# ProProject_2024__2024-10-06.net
KiCad netlist of a schematic drawn in EasyEDA Pro
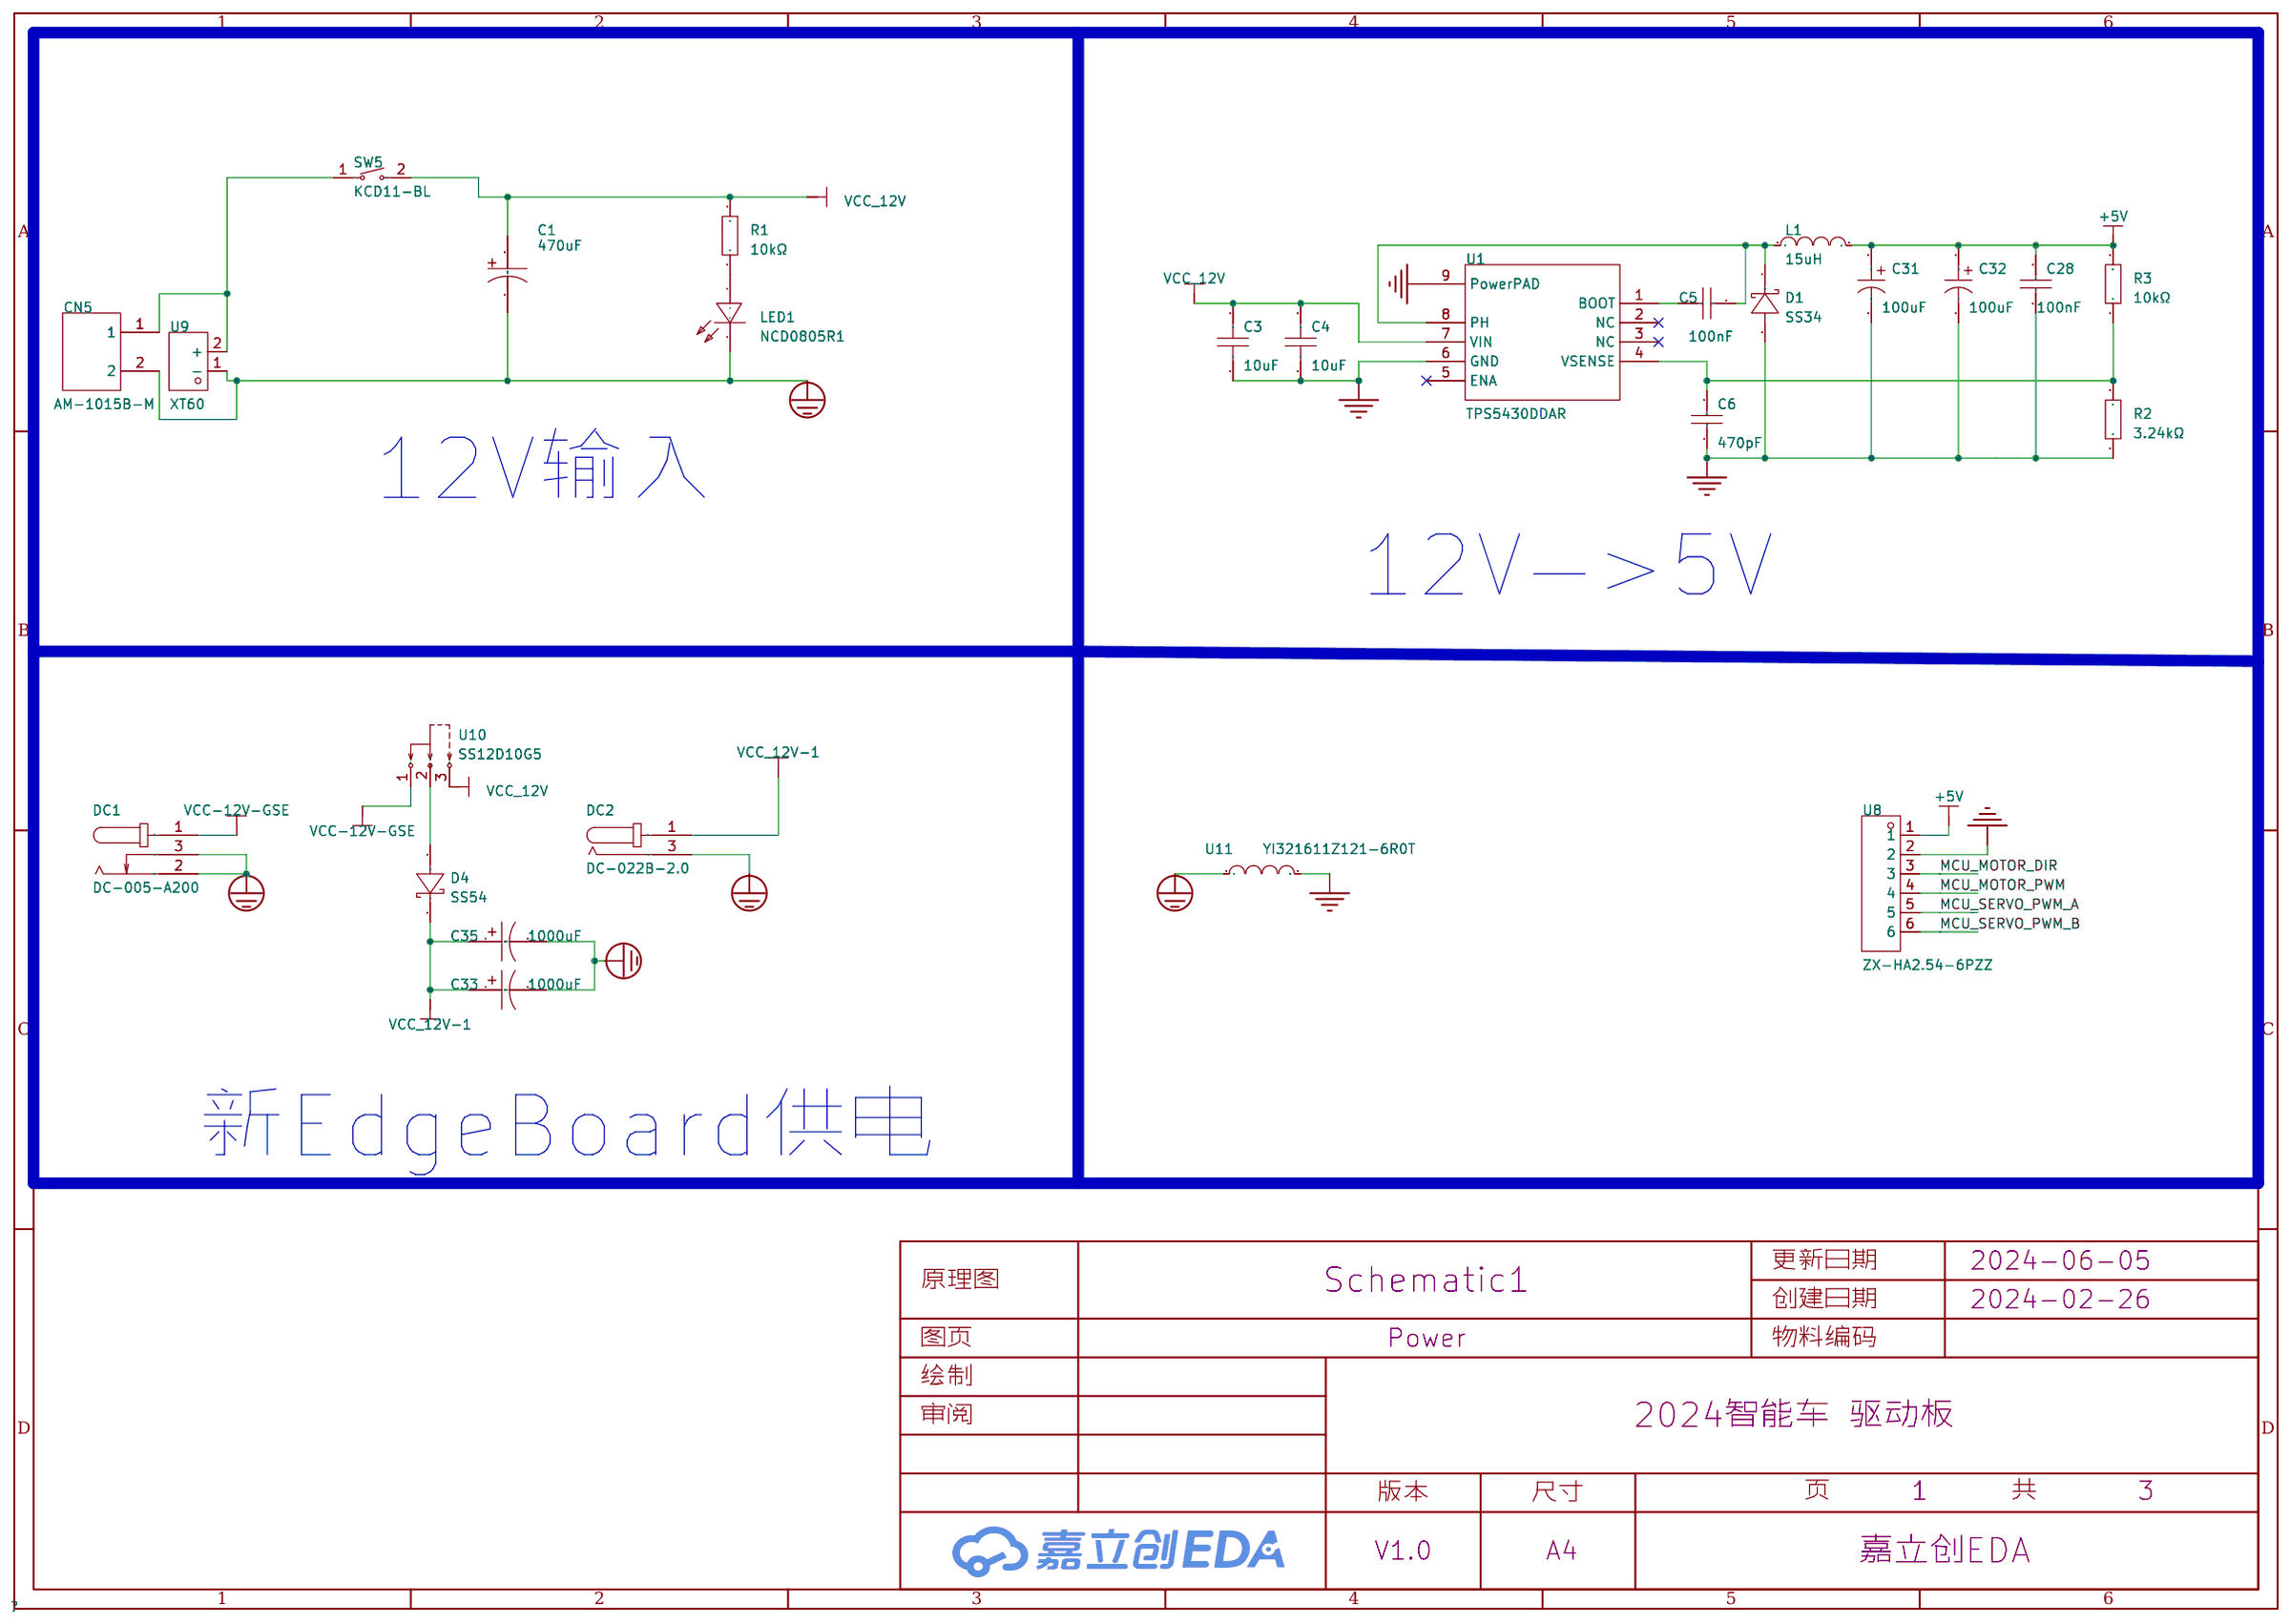
[diagram p0: Power]
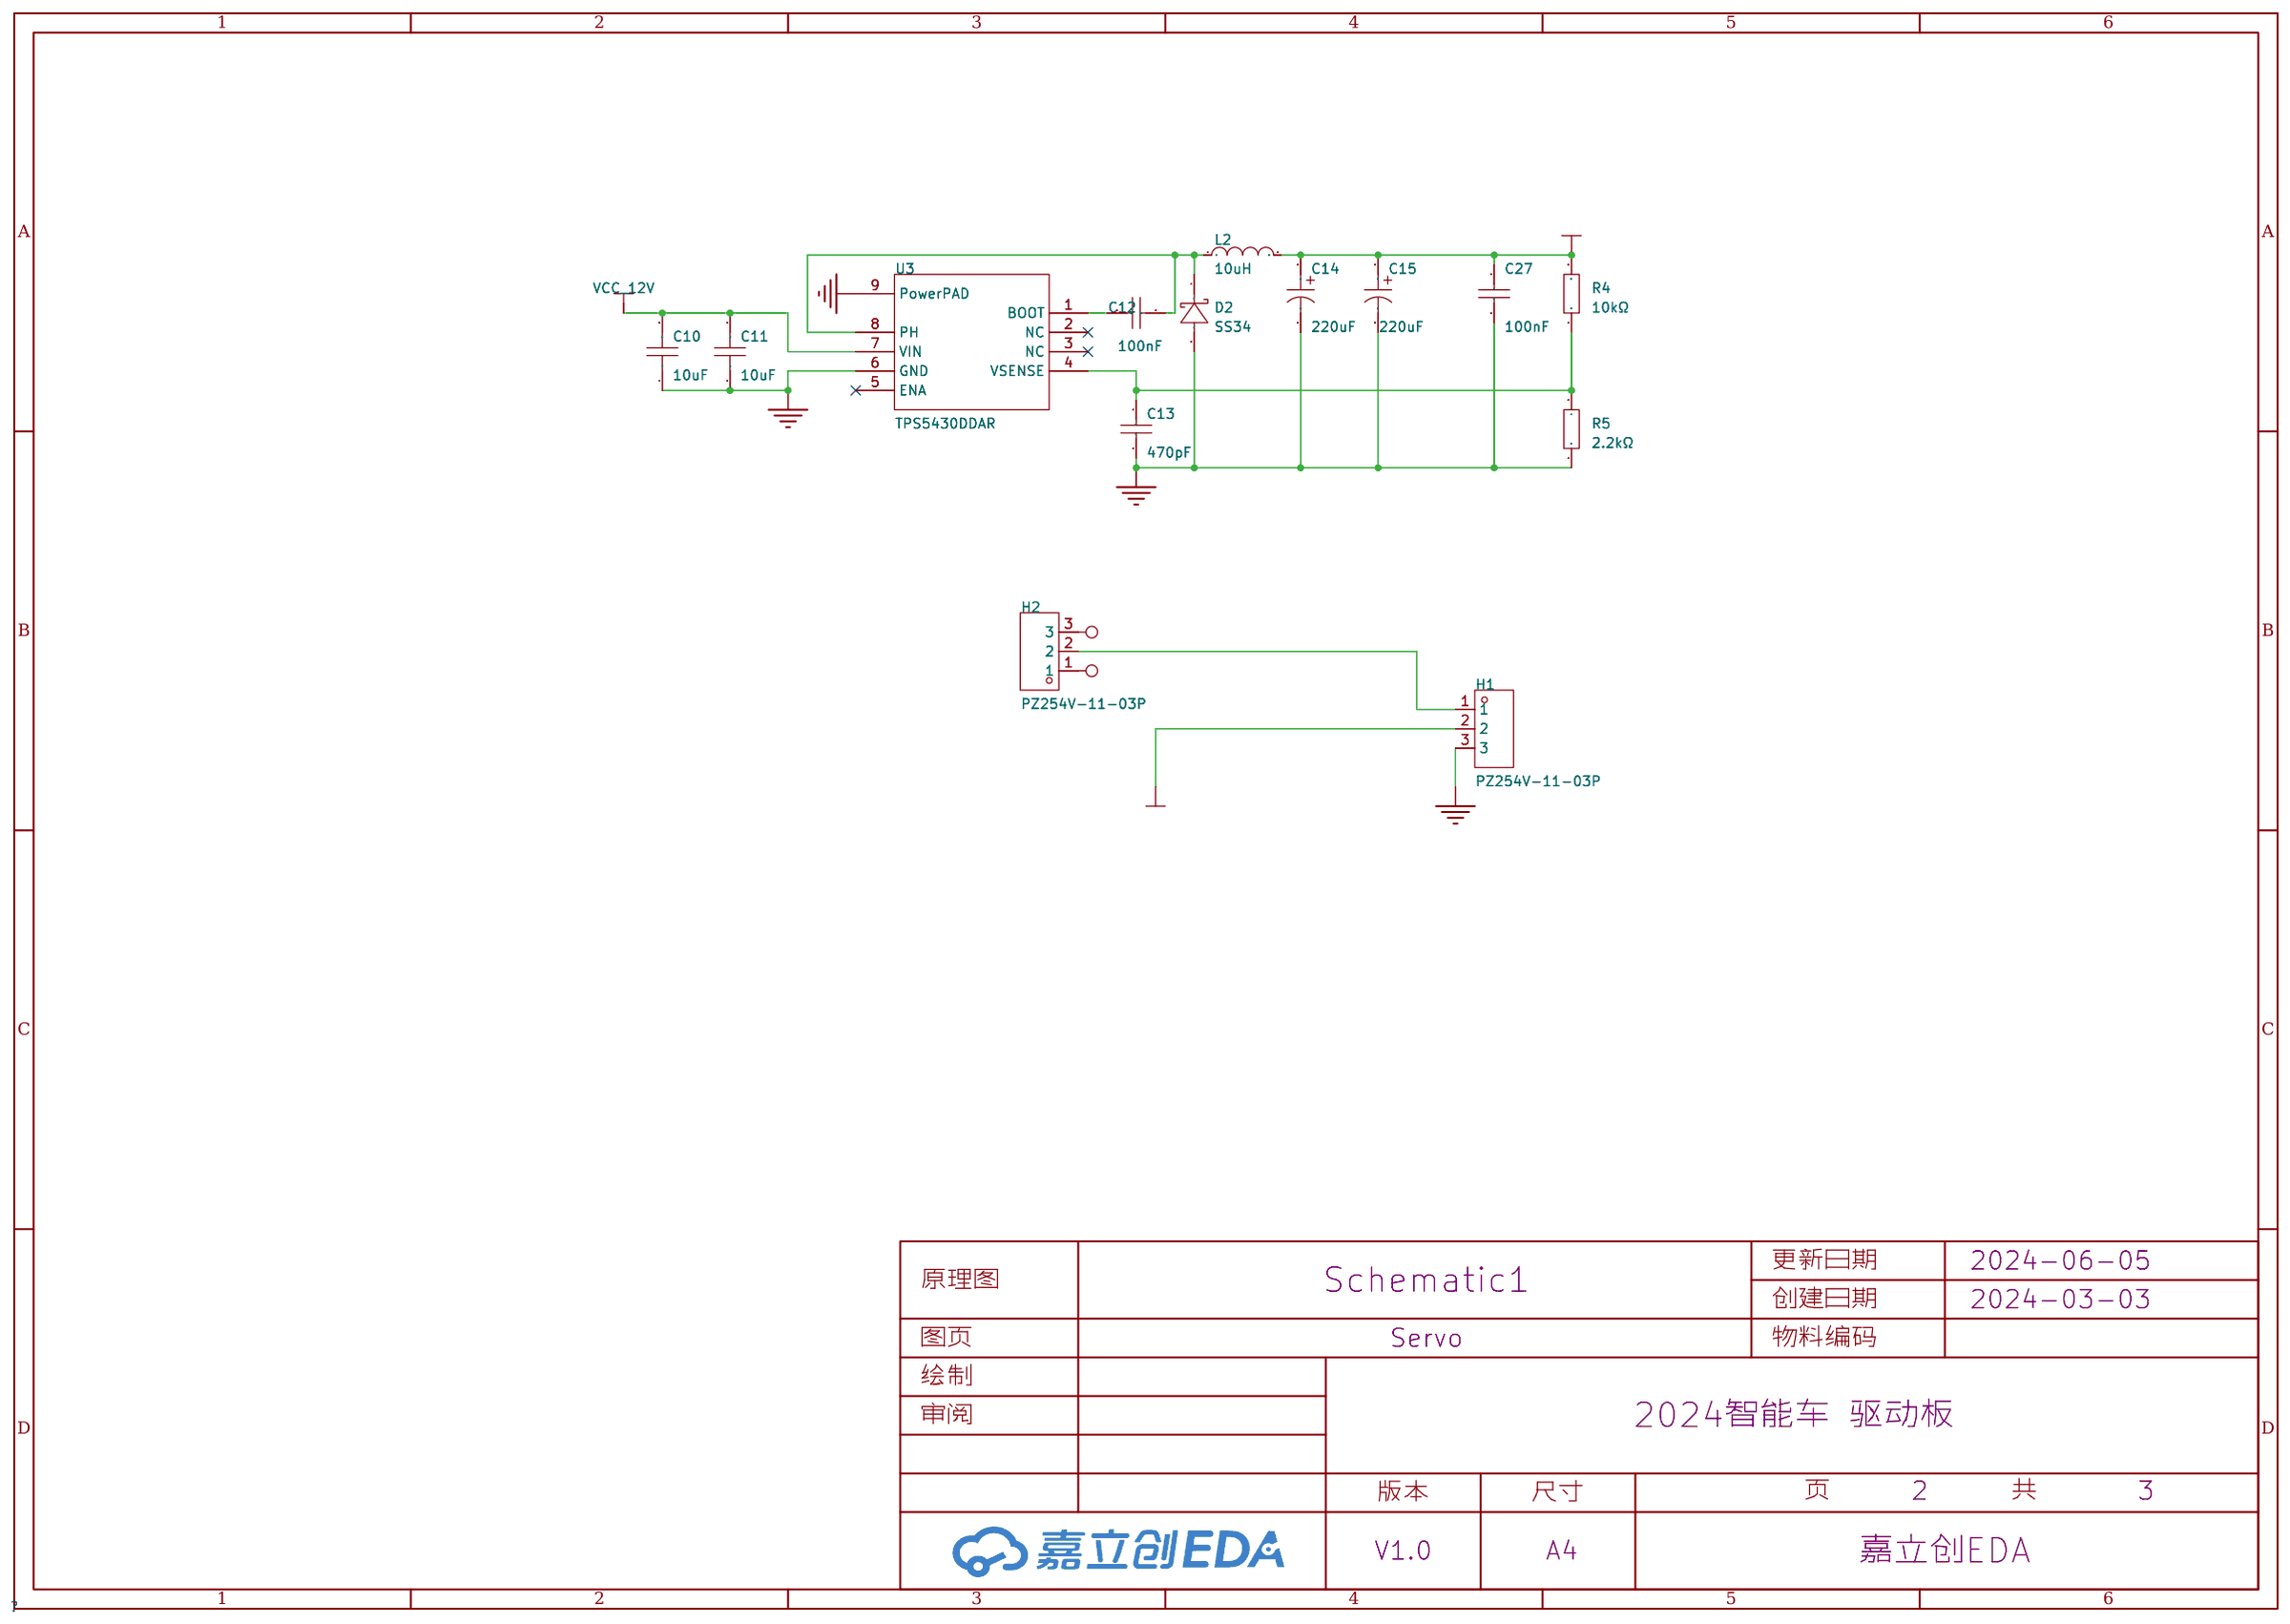
[diagram p1: Servo]
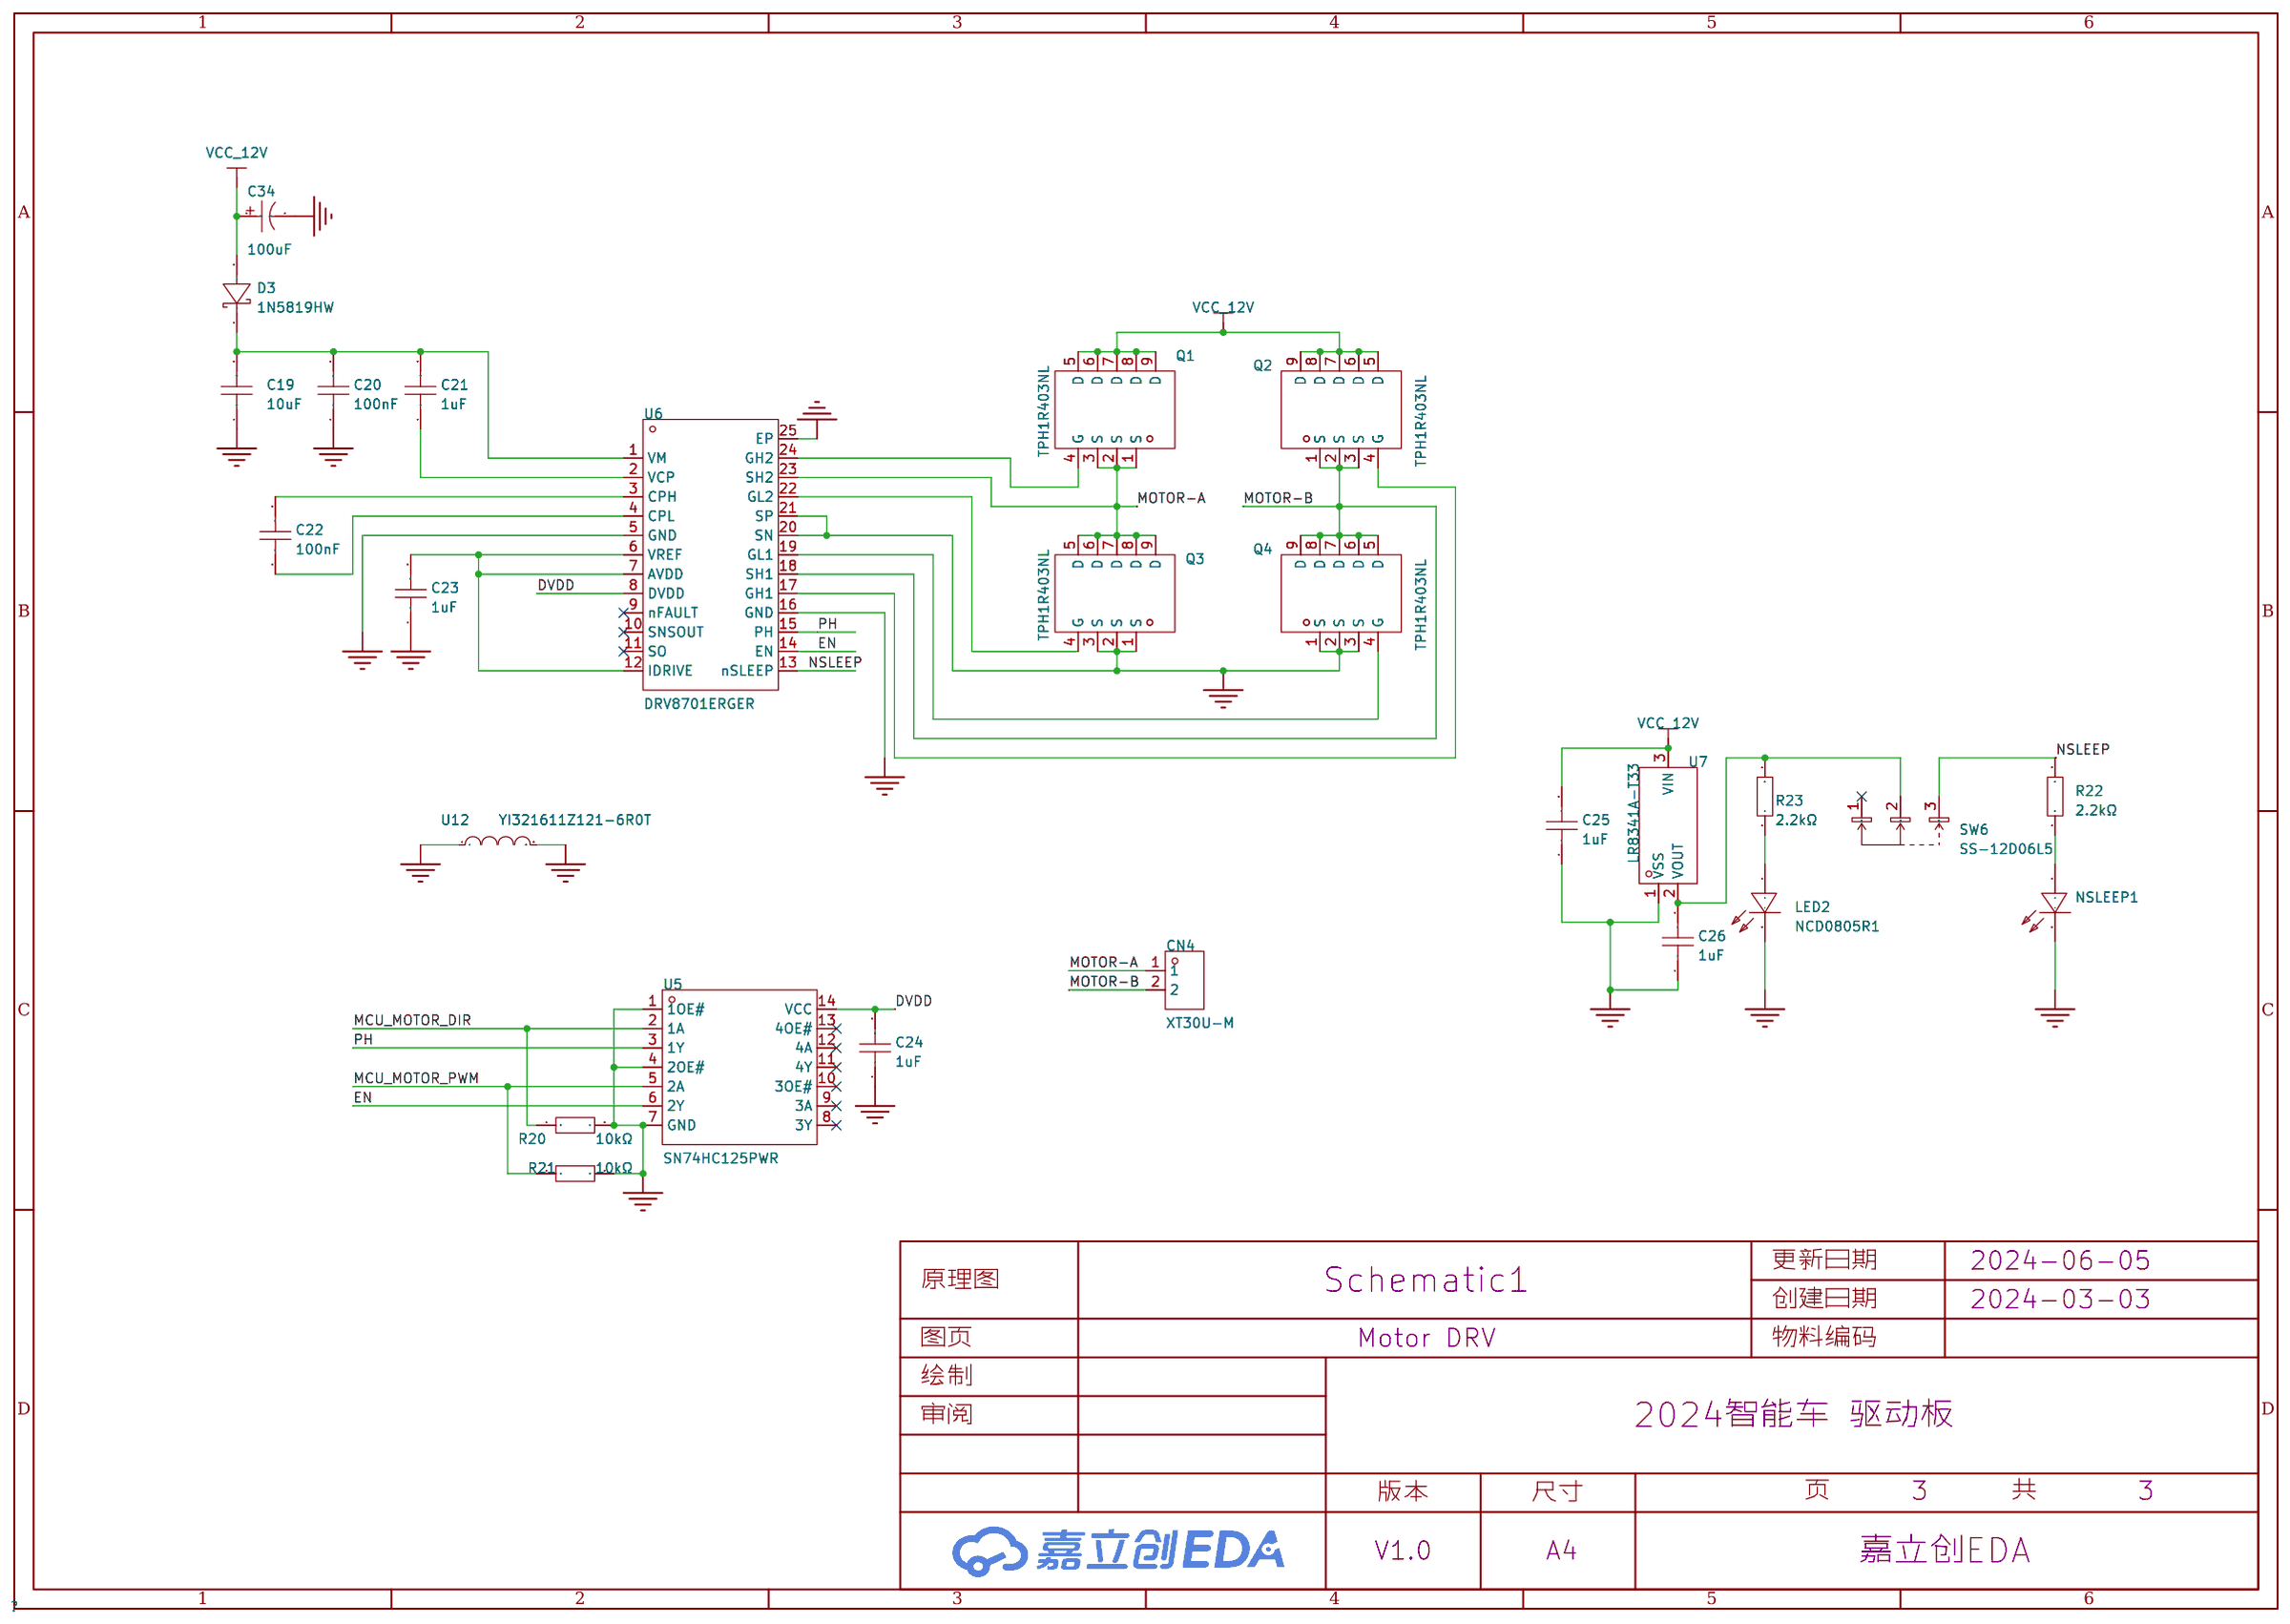
[diagram p2: Motor DRV]

(export (version "E")
  (design (tool "Eeschema 10.0.6"))
  (components
    (comp (ref "C1")
      (value "470uF")
      (footprint "easyedapro:CAP-TH_BD8.0-P3.50-D0.6-FD")
      (description "容值:470uF;精度:±20%;额定电压:25V;纹波电流:250mA@100kHz;等效串联电阻:-;")
      (fields
        (field (name "Manufacturer Part") "01EC1227SHC470UF25V")
        (field (name "Manufacturer") "KNSCHA(科尼盛)")
      )
      (libsource (lib "easyedapro") (part "01EC1227SHC470UF25V"))
    )
    (comp (ref "C3")
      (value "10uF")
      (footprint "easyedapro:C0805")
      (description "容值:10uF;精度:±10%;额定电压:25V;材质(温度系数):X5R;")
      (fields
        (field (name "Manufacturer Part") "CL21A106KAYNNNE")
        (field (name "Manufacturer") "SAMSUNG(三星)")
      )
      (libsource (lib "easyedapro") (part "CL21A106KAYNNNE"))
    )
    (comp (ref "C4")
      (value "10uF")
      (footprint "easyedapro:C0805")
      (description "容值:10uF;精度:±10%;额定电压:25V;材质(温度系数):X5R;")
      (fields
        (field (name "Manufacturer Part") "CL21A106KAYNNNE")
        (field (name "Manufacturer") "SAMSUNG(三星)")
      )
      (libsource (lib "easyedapro") (part "CL21A106KAYNNNE"))
    )
    (comp (ref "C5")
      (value "100nF")
      (footprint "easyedapro:C0603")
      (description "容值:100nF;精度:±10%;额定电压:50V;材质(温度系数):X7R;")
      (fields (field (name "Manufacturer Part") "0603B104K500NT") (field (name "Manufacturer") "FH(风华)"))
      (libsource (lib "easyedapro") (part "0603B104K500NT"))
    )
    (comp (ref "C6")
      (value "470pF")
      (footprint "easyedapro:C0603")
      (description "容值:470pF;精度:±10%;额定电压:50V;材质(温度系数):X7R;")
      (fields (field (name "Manufacturer Part") "0603B471K500NT") (field (name "Manufacturer") "FH(风华)"))
      (libsource (lib "easyedapro") (part "0603B471K500NT"))
    )
    (comp (ref "C28")
      (value "100nF")
      (footprint "easyedapro:C0603")
      (description "容值:100nF;精度:±10%;额定电压:50V;材质(温度系数):X7R;")
      (fields (field (name "Manufacturer Part") "0603B104K500NT") (field (name "Manufacturer") "FH(风华)"))
      (libsource (lib "easyedapro") (part "0603B104K500NT"))
    )
    (comp (ref "C31")
      (value "100uF")
      (footprint "easyedapro:CAP-SMD_BD6.3-L6.6-W6.6-LS7.2-FD")
      (description "容值:100uF;精度:±20%;额定电压:16V;纹波电流:93mA@120Hz;等效串联电阻:-;")
      (fields
        (field (name "Manufacturer Part") "RVT100UF16V67RV0016")
        (field (name "Manufacturer") "KNSCHA(科尼盛)")
      )
      (libsource (lib "easyedapro") (part "RVT100UF16V67RV0016"))
    )
    (comp (ref "C32")
      (value "100uF")
      (footprint "easyedapro:CAP-SMD_BD6.3-L6.6-W6.6-LS7.2-FD")
      (description "容值:100uF;精度:±20%;额定电压:16V;纹波电流:93mA@120Hz;等效串联电阻:-;")
      (fields
        (field (name "Manufacturer Part") "RVT100UF16V67RV0016")
        (field (name "Manufacturer") "KNSCHA(科尼盛)")
      )
      (libsource (lib "easyedapro") (part "RVT100UF16V67RV0016"))
    )
    (comp (ref "C33")
      (value "1000uF")
      (footprint "easyedapro:CAP-TH_BD13.0-P5.00-D0.6-FD")
      (description "容值:1000uF;精度:±20%;额定电压:35V;纹波电流:-;等效串联电阻:-;")
      (fields
        (field (name "Manufacturer Part") "SHF1000UF35V01EC4584")
        (field (name "Manufacturer") "KNSCHA(科尼盛)")
      )
      (libsource (lib "easyedapro") (part "SHF1000UF35V01EC4584"))
    )
    (comp (ref "C35")
      (value "1000uF")
      (footprint "easyedapro:CAP-TH_BD13.0-P5.00-D0.6-FD")
      (description "容值:1000uF;精度:±20%;额定电压:35V;纹波电流:-;等效串联电阻:-;")
      (fields
        (field (name "Manufacturer Part") "SHF1000UF35V01EC4584")
        (field (name "Manufacturer") "KNSCHA(科尼盛)")
      )
      (libsource (lib "easyedapro") (part "SHF1000UF35V01EC4584"))
    )
    (comp (ref "CN5")
      (value "AM-1015B-M")
      (footprint "easyedapro:CONN-TH_AM-1015B-M")
      (description "类别:-;类型1:-;")
      (fields (field (name "Manufacturer") "AMASS(艾迈斯)"))
      (libsource (lib "easyedapro") (part "AM-1015B-M"))
    )
    (comp (ref "D1")
      (value "SS34")
      (footprint "easyedapro:SMA_L4.3-W2.5-LS5.0-RD")
      (description "二极管配置:独立式;正向压降(Vf):550mV@3A;直流反向耐压(Vr):40V;平均整流电流(Io):3A;")
      (fields (field (name "Manufacturer") "TWGMC(台湾迪嘉)"))
      (libsource (lib "easyedapro") (part "SS34_C727060"))
    )
    (comp (ref "D4")
      (value "SS54")
      (footprint "easyedapro:SMA_L4.3-W2.6-LS5.0-RD")
      (description "二极管配置:独立式;正向压降(Vf):550mV@5A;直流反向耐压(Vr):40V;平均整流电流(Io):5A;")
      (fields (field (name "Manufacturer") "TWGMC(台湾迪嘉)"))
      (libsource (lib "easyedapro") (part "SS54_C727065"))
    )
    (comp (ref "DC1")
      (value "DC-005-A200")
      (footprint "easyedapro:DC-IN-TH_DC-005-A200")
      (description "连接器类型:DC电源插座;安装方式:弯插;触点内径:2mm;触点外径:6.4mm;额定电流:3A;额定电压:30V;工作温度范围:-20°C~+70°C;")
      (fields (field (name "Manufacturer") "XUNPU(讯普)"))
      (libsource (lib "easyedapro") (part "DC-005-A200"))
    )
    (comp (ref "DC2")
      (value "DC-022B-2.0")
      (footprint "easyedapro:DC-IN-TH_DC-022B-2.0")
      (fields (field (name "Manufacturer") "XKB Connectivity(中国星坤)"))
      (libsource (lib "easyedapro") (part "DC-022B-2.0"))
    )
    (comp (ref "L1")
      (value "15uH")
      (footprint "easyedapro:IND-SMD_L7.0-W6.6_FXL0630")
      (description "电感值:15uH;精度:±20%;额定电流:3A;饱和电流(Isat):4.5A;类型:一体成型电感;")
      (fields (field (name "Manufacturer Part") "FXL0630-150-M") (field (name "Manufacturer") "cjiang(长江微电)"))
      (libsource (lib "easyedapro") (part "FXL0630-150-M"))
    )
    (comp (ref "LED1")
      (value "NCD0805R1")
      (footprint "easyedapro:LED0805-R-RD")
      (fields (field (name "Manufacturer") "国星光电"))
      (libsource (lib "easyedapro") (part "FC-2012HRK-620D"))
    )
    (comp (ref "R1")
      (value "10kΩ")
      (footprint "easyedapro:R0805")
      (description "电阻类型:厚膜电阻;阻值:10kΩ;精度:±1%;功率:125mW;最大工作电压:150V;温度系数:±100ppm/°C;")
      (fields
        (field (name "Manufacturer Part") "0805W8F1002T5E")
        (field (name "Manufacturer") "UNI-ROYAL(厚声)")
      )
      (libsource (lib "easyedapro") (part "0805W8F1002T5E"))
    )
    (comp (ref "R2")
      (value "3.24kΩ")
      (footprint "easyedapro:R0603")
      (description "电阻类型:厚膜电阻;阻值:3.24kΩ;精度:±1%;功率:100mW;最大工作电压:75V;温度系数:±100ppm/°C;")
      (fields
        (field (name "Manufacturer Part") "0603WAF3241T5E")
        (field (name "Manufacturer") "UNI-ROYAL(厚声)")
      )
      (libsource (lib "easyedapro") (part "0603WAF3241T5E"))
    )
    (comp (ref "R3")
      (value "10kΩ")
      (footprint "easyedapro:R0603")
      (description "电阻类型:厚膜电阻;阻值:10kΩ;精度:±1%;功率:100mW;最大工作电压:75V;温度系数:±100ppm/°C;")
      (fields
        (field (name "Manufacturer Part") "0603WAF1002T5E")
        (field (name "Manufacturer") "UNI-ROYAL(厚声)")
      )
      (libsource (lib "easyedapro") (part "0603WAF1002T5E"))
    )
    (comp (ref "SW5")
      (value "KCD11-BL")
      (footprint "easyedapro:SW-TH_KCD11-BL")
      (description "带灯:无;引脚样式:焊片;额定电流:3A;额定电压(AC):250V;额定电压(DC):-;电路结构:单刀单掷;机械寿命:1万次;")
      (fields (field (name "Manufacturer") "SHOU HAN(首韩)"))
      (libsource (lib "easyedapro") (part "KCD11-BL"))
    )
    (comp (ref "U1")
      (value "TPS5430DDAR")
      (footprint "easyedapro:ESOP-8_L4.9-W3.9-P1.27-LS6.0-TL-EP")
      (description "功能类型:降压型;输出类型:可调;输入电压:5.5V~36V;输出电压:1.221V~32.04V;输出电流(最大值):3A;")
      (fields (field (name "Manufacturer") "TI(德州仪器)"))
      (libsource (lib "easyedapro") (part "TPS5430DDAR"))
    )
    (comp (ref "U8")
      (value "ZX-HA2.54-6PZZ")
      (footprint "easyedapro:CONN-TH_6P-P2.50_ZX-HA2.54-6PZZ")
      (fields (field (name "Manufacturer") "Megastar(兆星)"))
      (libsource (lib "easyedapro") (part "ZX-HA2.54-6PZZ"))
    )
    (comp (ref "U9")
      (value "XT60")
      (footprint "easyedapro:CONN-TH_XT60")
      (description "类别:-;类型1:-;")
      (fields (field (name "Manufacturer") "AMASS(艾迈斯)"))
      (libsource (lib "easyedapro") (part "XT60"))
    )
    (comp (ref "U10")
      (value "SS12D10G5")
      (footprint "easyedapro:SW-TH_SHOU-HAN_SS12D10G4")
      (description "电路结构:单刀双掷;安装方式:直插;额定电流(DC):2A;额定电压(DC):125V;机械寿命:3千次;")
      (fields (field (name "Manufacturer") "SHOU HAN(首韩)"))
      (libsource (lib "easyedapro") (part "SS12D10G5"))
    )
    (comp (ref "U11")
      (value "YI321611Z121-6R0T")
      (footprint "easyedapro:L1206")
      (description "标称阻抗@测试频率:120Ω@100MHz;误差:±25%;直流电阻(RDC):20mΩ;")
      (fields (field (name "Manufacturer") "YJYCOIN(益嘉源)"))
      (libsource (lib "easyedapro") (part "YI321611Z121-6R0T"))
    )
    (comp (ref "C10")
      (value "10uF")
      (footprint "easyedapro:C0805")
      (description "容值:10uF;精度:±10%;额定电压:25V;材质(温度系数):X5R;")
      (fields
        (field (name "Manufacturer Part") "CL21A106KAYNNNE")
        (field (name "Manufacturer") "SAMSUNG(三星)")
      )
      (libsource (lib "easyedapro") (part "CL21A106KAYNNNE"))
    )
    (comp (ref "C11")
      (value "10uF")
      (footprint "easyedapro:C0805")
      (description "容值:10uF;精度:±10%;额定电压:25V;材质(温度系数):X5R;")
      (fields
        (field (name "Manufacturer Part") "CL21A106KAYNNNE")
        (field (name "Manufacturer") "SAMSUNG(三星)")
      )
      (libsource (lib "easyedapro") (part "CL21A106KAYNNNE"))
    )
    (comp (ref "C12")
      (value "100nF")
      (footprint "easyedapro:C0603")
      (description "容值:100nF;精度:±10%;额定电压:50V;材质(温度系数):X7R;")
      (fields (field (name "Manufacturer Part") "0603B104K500NT") (field (name "Manufacturer") "FH(风华)"))
      (libsource (lib "easyedapro") (part "0603B104K500NT"))
    )
    (comp (ref "C13")
      (value "470pF")
      (footprint "easyedapro:C0603")
      (description "容值:470pF;精度:±10%;额定电压:50V;材质(温度系数):X7R;")
      (fields (field (name "Manufacturer Part") "0603B471K500NT") (field (name "Manufacturer") "FH(风华)"))
      (libsource (lib "easyedapro") (part "0603B471K500NT"))
    )
    (comp (ref "C14")
      (value "220uF")
      (footprint "easyedapro:CAP-SMD_BD6.3-L6.6-W6.6-FD")
      (description "容值:220uF;精度:±20%;额定电压:16V;纹波电流:110mA@120Hz;等效串联电阻:-;")
      (fields
        (field (name "Manufacturer Part") "RVT220UF16V67RV0015")
        (field (name "Manufacturer") "KNSCHA(科尼盛)")
      )
      (libsource (lib "easyedapro") (part "RVT220UF16V67RV0015"))
    )
    (comp (ref "C15")
      (value "220uF")
      (footprint "easyedapro:CAP-SMD_BD6.3-L6.6-W6.6-FD")
      (description "容值:220uF;精度:±20%;额定电压:16V;纹波电流:110mA@120Hz;等效串联电阻:-;")
      (fields
        (field (name "Manufacturer Part") "RVT220UF16V67RV0015")
        (field (name "Manufacturer") "KNSCHA(科尼盛)")
      )
      (libsource (lib "easyedapro") (part "RVT220UF16V67RV0015"))
    )
    (comp (ref "C27")
      (value "100nF")
      (footprint "easyedapro:C0603")
      (description "容值:100nF;精度:±10%;额定电压:50V;材质(温度系数):X7R;")
      (fields (field (name "Manufacturer Part") "0603B104K500NT") (field (name "Manufacturer") "FH(风华)"))
      (libsource (lib "easyedapro") (part "0603B104K500NT"))
    )
    (comp (ref "D2")
      (value "SS34")
      (footprint "easyedapro:SMA_L4.3-W2.5-LS5.0-RD")
      (description "二极管配置:独立式;正向压降(Vf):550mV@3A;直流反向耐压(Vr):40V;平均整流电流(Io):3A;")
      (fields (field (name "Manufacturer") "TWGMC(台湾迪嘉)"))
      (libsource (lib "easyedapro") (part "SS34_C727060"))
    )
    (comp (ref "H1")
      (value "PZ254V-11-03P")
      (footprint "easyedapro:HDR-TH_3P-P2.54-V-M")
      (fields (field (name "Manufacturer") "XFCN(兴飞)"))
      (libsource (lib "easyedapro") (part "PZ254V-11-03P_C2937625"))
    )
    (comp (ref "H2")
      (value "PZ254V-11-03P")
      (footprint "easyedapro:HDR-TH_3P-P2.54-V-M")
      (fields (field (name "Manufacturer") "XFCN(兴飞)"))
      (libsource (lib "easyedapro") (part "PZ254V-11-03P_C2937625"))
    )
    (comp (ref "L2")
      (value "10uH")
      (footprint "easyedapro:IND-SMD_L7.0-W6.6_FXL0650")
      (description "电感值:10uH;精度:±20%;额定电流:4.5A;饱和电流(Isat):5.3A;类型:一体成型电感;")
      (fields (field (name "Manufacturer Part") "FXL0650-100-M") (field (name "Manufacturer") "cjiang(长江微电)"))
      (libsource (lib "easyedapro") (part "FXL0650-100-M"))
    )
    (comp (ref "R4")
      (value "10kΩ")
      (footprint "easyedapro:R0603")
      (description "电阻类型:厚膜电阻;阻值:10kΩ;精度:±1%;功率:100mW;最大工作电压:75V;温度系数:±100ppm/°C;")
      (fields
        (field (name "Manufacturer Part") "0603WAF1002T5E")
        (field (name "Manufacturer") "UNI-ROYAL(厚声)")
      )
      (libsource (lib "easyedapro") (part "0603WAF1002T5E"))
    )
    (comp (ref "R5")
      (value "2.2kΩ")
      (footprint "easyedapro:R0603")
      (description "电阻类型:厚膜电阻;阻值:2.2kΩ;精度:±1%;功率:100mW;")
      (fields
        (field (name "Manufacturer Part") "0603WAF2201T5E")
        (field (name "Manufacturer") "UNI-ROYAL(厚声)")
      )
      (libsource (lib "easyedapro") (part "0603WAF2201T5E"))
    )
    (comp (ref "U3")
      (value "TPS5430DDAR")
      (footprint "easyedapro:ESOP-8_L4.9-W3.9-P1.27-LS6.0-TL-EP")
      (description "功能类型:降压型;输出类型:可调;输入电压:5.5V~36V;输出电压:1.221V~32.04V;输出电流(最大值):3A;")
      (fields (field (name "Manufacturer") "TI(德州仪器)"))
      (libsource (lib "easyedapro") (part "TPS5430DDAR"))
    )
    (comp (ref "C19")
      (value "10uF")
      (fields
        (field (name "Manufacturer Part") "GCM21BR7YA105KA55L")
        (field (name "Manufacturer") "muRata(村田)")
      )
      (libsource (lib "easyedapro") (part "capacitance"))
    )
    (comp (ref "C20")
      (value "100nF")
      (fields
        (field (name "Manufacturer Part") "CC0603KRX7R9BB104")
        (field (name "Manufacturer") "YAGEO(国巨)")
      )
      (libsource (lib "easyedapro") (part "capacitance"))
    )
    (comp (ref "C21")
      (value "1uF")
      (footprint "easyedapro:C0603")
      (libsource (lib "easyedapro") (part "capacitance"))
    )
    (comp (ref "C22")
      (value "100nF")
      (fields
        (field (name "Manufacturer Part") "CC0603KRX7R9BB104")
        (field (name "Manufacturer") "YAGEO(国巨)")
      )
      (libsource (lib "easyedapro") (part "capacitance"))
    )
    (comp (ref "C23")
      (value "1uF")
      (footprint "easyedapro:C0603")
      (libsource (lib "easyedapro") (part "capacitance"))
    )
    (comp (ref "C24")
      (value "1uF")
      (footprint "easyedapro:C0603")
      (fields
        (field (name "Manufacturer Part") "CL10A105KB8NNNC")
        (field (name "Manufacturer") "SAMSUNG(三星)")
      )
      (libsource (lib "easyedapro") (part "capacitance"))
    )
    (comp (ref "C25")
      (value "1uF")
      (footprint "easyedapro:C0603")
      (libsource (lib "easyedapro") (part "capacitance"))
    )
    (comp (ref "C26")
      (value "1uF")
      (footprint "easyedapro:C0603")
      (libsource (lib "easyedapro") (part "capacitance"))
    )
    (comp (ref "C34")
      (value "100uF")
      (footprint "easyedapro:CAP-TH_BD6.3-P2.50-D1.0-FD")
      (description "容值:100uF;精度:±20%;额定电压:35V;纹波电流:270mA@120Hz;")
      (fields
        (field (name "Manufacturer Part") "35ZLH100MEFC6.3X11")
        (field (name "Manufacturer") "rubycon(红宝石)")
      )
      (libsource (lib "easyedapro") (part "35ZLH100MEFC6.3X11"))
    )
    (comp (ref "CN4")
      (value "XT30U-M")
      (footprint "easyedapro:CONN-TH_XT30U-M")
      (description "类别:-;类型1:-;")
      (fields (field (name "Manufacturer") "AMASS(艾迈斯)"))
      (libsource (lib "easyedapro") (part "XT30U-M"))
    )
    (comp (ref "D3")
      (value "1N5819HW")
      (footprint "easyedapro:SOD-123_L2.7-W1.6-LS3.7-RD-1")
      (description "二极管配置:-;直流反向耐压(Vr):40V;平均整流电流(Io):1A;正向压降(Vf):900mV@3A;反向电流(Ir):1mA@40V;")
      (fields (field (name "Manufacturer") "TECH PUBLIC(台舟)"))
      (libsource (lib "easyedapro") (part "1N5819HW"))
    )
    (comp (ref "LED2")
      (value "NCD0805R1")
      (footprint "easyedapro:LED0805-R-RD")
      (fields (field (name "Manufacturer") "国星光电"))
      (libsource (lib "easyedapro") (part "FC-2012HRK-620D"))
    )
    (comp (ref "NSLEEP1")
      (value "NCD0805R1")
      (footprint "easyedapro:LED0805-R-RD")
      (description "发光颜色:红灯;")
      (fields (field (name "Manufacturer") "国星光电"))
      (libsource (lib "easyedapro") (part "FC-2012HRK-620D"))
    )
    (comp (ref "Q1")
      (value "TPH1R403NL")
      (footprint "easyedapro:DSOP-8_L5.0-W5.0-P1.27-LS6.0-BL-EP")
      (fields (field (name "Manufacturer") "TOSHIBA(东芝)"))
      (libsource (lib "easyedapro") (part "TPH1R403NL"))
    )
    (comp (ref "Q2")
      (value "TPH1R403NL")
      (footprint "easyedapro:DSOP-8_L5.0-W5.0-P1.27-LS6.0-BL-EP")
      (fields (field (name "Manufacturer") "TOSHIBA(东芝)"))
      (libsource (lib "easyedapro") (part "TPH1R403NL"))
    )
    (comp (ref "Q3")
      (value "TPH1R403NL")
      (footprint "easyedapro:DSOP-8_L5.0-W5.0-P1.27-LS6.0-BL-EP")
      (fields (field (name "Manufacturer") "TOSHIBA(东芝)"))
      (libsource (lib "easyedapro") (part "TPH1R403NL"))
    )
    (comp (ref "Q4")
      (value "TPH1R403NL")
      (footprint "easyedapro:DSOP-8_L5.0-W5.0-P1.27-LS6.0-BL-EP")
      (fields (field (name "Manufacturer") "TOSHIBA(东芝)"))
      (libsource (lib "easyedapro") (part "TPH1R403NL"))
    )
    (comp (ref "R20")
      (value "10kΩ")
      (description "电阻类型:厚膜电阻;阻值:10kΩ;精度:±1%;功率:100mW;")
      (fields
        (field (name "Manufacturer Part") "0603WAF1002T5E")
        (field (name "Manufacturer") "UNI-ROYAL(厚声)")
      )
      (libsource (lib "easyedapro") (part "电阻"))
    )
    (comp (ref "R21")
      (value "10kΩ")
      (description "电阻类型:厚膜电阻;阻值:10kΩ;精度:±1%;功率:100mW;")
      (fields
        (field (name "Manufacturer Part") "0603WAF1002T5E")
        (field (name "Manufacturer") "UNI-ROYAL(厚声)")
      )
      (libsource (lib "easyedapro") (part "电阻"))
    )
    (comp (ref "R22")
      (value "2.2kΩ")
      (fields
        (field (name "Manufacturer Part") "0603WAF2201T5E")
        (field (name "Manufacturer") "UNI-ROYAL(厚声)")
      )
      (libsource (lib "easyedapro") (part "电阻"))
    )
    (comp (ref "R23")
      (value "2.2kΩ")
      (fields
        (field (name "Manufacturer Part") "0603WAF2201T5E")
        (field (name "Manufacturer") "UNI-ROYAL(厚声)")
      )
      (libsource (lib "easyedapro") (part "电阻"))
    )
    (comp (ref "SW6")
      (value "SS-12D06L5")
      (footprint "easyedapro:SW-TH_3P-P4.70_L11.1-W12.7")
      (description "电路结构:单刀双掷;安装方式:侧插;开关颜色:黑色;额定电流(DC):3A;额定电压(DC):250V;额定电流(AC):3A;额定电压(AC):250V;机械寿命:1万次;")
      (fields (field (name "Manufacturer") "XKB Connectivity(中国星坤)"))
      (libsource (lib "easyedapro") (part "SS-12D06L5"))
    )
    (comp (ref "U5")
      (value "SN74HC125PWR")
      (footprint "easyedapro:TSSOP-14_L5.0-W4.4-P0.65-LS6.5-BL")
      (description "类型:缓冲器，非反相;电源电压:2V~6V;输入类型:-;输出类型:三态;低电平输出电流(IOL):7.8mA;高电平输出电流(IOH):7.8mA;工作温度:-40°C~+85°C;")
      (fields (field (name "Manufacturer") "TI(德州仪器)"))
      (libsource (lib "easyedapro") (part "SN74HC125PWR"))
    )
    (comp (ref "U6")
      (value "DRV8701ERGER")
      (footprint "easyedapro:VQFN-24_L4.0-W4.0-P0.50-BL-EP2.5")
      (description "类型:有刷直流电机;电源电压:5.9V~45V;输出电流:-;接口:并行;")
      (fields (field (name "Manufacturer") "TI(德州仪器)"))
      (libsource (lib "easyedapro") (part "DRV8701ERGER"))
    )
    (comp (ref "U7")
      (value "LR8341A-T33")
      (footprint "easyedapro:SOT-23-3L_L2.9-W1.6-P1.90-LS2.8-BL")
      (description "输出类型:固定;输出极性:正;最大输入电压:40V;输出电压:3.3V;输出电流:100mA;电源纹波抑制比(PSRR):55dB@(1kHz);")
      (fields (field (name "Manufacturer") "LR(朗瑞)"))
      (libsource (lib "easyedapro") (part "LR8341A-T33"))
    )
    (comp (ref "U12")
      (value "YI321611Z121-6R0T")
      (footprint "easyedapro:L1206")
      (description "标称阻抗@测试频率:120Ω@100MHz;误差:±25%;直流电阻(RDC):20mΩ;")
      (fields (field (name "Manufacturer") "YJYCOIN(益嘉源)"))
      (libsource (lib "easyedapro") (part "YI321611Z121-6R0T"))
    )
  )
  (nets
    (net (code "1") (name "+5V") (class "Default")
      (node (ref "C28") (pin "1") (pinfunction "1_1") (pintype "input"))
      (node (ref "C31") (pin "1") (pinfunction "1_1") (pintype "input"))
      (node (ref "C32") (pin "1") (pinfunction "1_1") (pintype "input"))
      (node (ref "L1") (pin "2") (pinfunction "2_2") (pintype "unspecified"))
      (node (ref "R3") (pin "2") (pinfunction "2_2") (pintype "input"))
      (node (ref "U8") (pin "1") (pinfunction "1_1") (pintype "unspecified"))
    )
    (net (code "2") (name "DVDD") (class "Default")
      (node (ref "C24") (pin "2") (pinfunction "2_2") (pintype "input"))
      (node (ref "U5") (pin "14") (pinfunction "VCC_14") (pintype "input"))
      (node (ref "U6") (pin "8") (pinfunction "DVDD_8") (pintype "input"))
    )
    (net (code "3") (name "EN") (class "Default")
      (node (ref "U5") (pin "6") (pinfunction "2Y_6") (pintype "input"))
      (node (ref "U6") (pin "14") (pinfunction "EN_14") (pintype "input"))
    )
    (net (code "4") (name "GND") (class "Default")
      (node (ref "C10") (pin "1") (pinfunction "1_1") (pintype "unspecified"))
      (node (ref "C11") (pin "1") (pinfunction "1_1") (pintype "unspecified"))
      (node (ref "C13") (pin "1") (pinfunction "1_1") (pintype "input"))
      (node (ref "C14") (pin "2") (pinfunction "2_2") (pintype "input"))
      (node (ref "C15") (pin "2") (pinfunction "2_2") (pintype "input"))
      (node (ref "C27") (pin "2") (pinfunction "2_2") (pintype "input"))
      (node (ref "C28") (pin "2") (pinfunction "2_2") (pintype "input"))
      (node (ref "C3") (pin "1") (pinfunction "1_1") (pintype "unspecified"))
      (node (ref "C31") (pin "2") (pinfunction "2_2") (pintype "input"))
      (node (ref "C32") (pin "2") (pinfunction "2_2") (pintype "input"))
      (node (ref "C4") (pin "1") (pinfunction "1_1") (pintype "unspecified"))
      (node (ref "C6") (pin "1") (pinfunction "1_1") (pintype "input"))
      (node (ref "D1") (pin "2") (pinfunction "A_2") (pintype "unspecified"))
      (node (ref "D2") (pin "2") (pinfunction "A_2") (pintype "unspecified"))
      (node (ref "H1") (pin "3") (pinfunction "3_3") (pintype "unspecified"))
      (node (ref "R2") (pin "1") (pinfunction "1_1") (pintype "input"))
      (node (ref "R5") (pin "1") (pinfunction "1_1") (pintype "input"))
      (node (ref "U1") (pin "6") (pinfunction "GND_6") (pintype "unspecified"))
      (node (ref "U1") (pin "9") (pinfunction "PowerPAD_9") (pintype "unspecified"))
      (node (ref "U11") (pin "2") (pinfunction "2_2") (pintype "unspecified"))
      (node (ref "U12") (pin "1") (pinfunction "1_1") (pintype "unspecified"))
      (node (ref "U3") (pin "6") (pinfunction "GND_6") (pintype "unspecified"))
      (node (ref "U3") (pin "9") (pinfunction "PowerPAD_9") (pintype "unspecified"))
      (node (ref "U8") (pin "2") (pinfunction "2_2") (pintype "unspecified"))
    )
    (net (code "5") (name "GND_DRV") (class "Default")
      (node (ref "C19") (pin "1") (pinfunction "1_1") (pintype "input"))
      (node (ref "C20") (pin "1") (pinfunction "1_1") (pintype "input"))
      (node (ref "C23") (pin "1") (pinfunction "1_1") (pintype "input"))
      (node (ref "C24") (pin "1") (pinfunction "1_1") (pintype "input"))
      (node (ref "C25") (pin "1") (pinfunction "1_1") (pintype "input"))
      (node (ref "C26") (pin "1") (pinfunction "1_1") (pintype "input"))
      (node (ref "C34") (pin "2") (pinfunction "2_2") (pintype "input"))
      (node (ref "LED2") (pin "2") (pinfunction "-_2") (pintype "unspecified"))
      (node (ref "NSLEEP1") (pin "2") (pinfunction "-_2") (pintype "unspecified"))
      (node (ref "Q3") (pin "1") (pinfunction "S_1") (pintype "input"))
      (node (ref "Q3") (pin "2") (pinfunction "S_2") (pintype "input"))
      (node (ref "Q3") (pin "3") (pinfunction "S_3") (pintype "input"))
      (node (ref "Q4") (pin "1") (pinfunction "S_1") (pintype "input"))
      (node (ref "Q4") (pin "2") (pinfunction "S_2") (pintype "input"))
      (node (ref "Q4") (pin "3") (pinfunction "S_3") (pintype "input"))
      (node (ref "R20") (pin "2") (pinfunction "2_2") (pintype "input"))
      (node (ref "R21") (pin "2") (pinfunction "2_2") (pintype "input"))
      (node (ref "U12") (pin "2") (pinfunction "2_2") (pintype "unspecified"))
      (node (ref "U5") (pin "1") (pinfunction "1OE#_1") (pintype "input"))
      (node (ref "U5") (pin "4") (pinfunction "2OE#_4") (pintype "input"))
      (node (ref "U5") (pin "7") (pinfunction "GND_7") (pintype "input"))
      (node (ref "U6") (pin "16") (pinfunction "GND_16") (pintype "input"))
      (node (ref "U6") (pin "20") (pinfunction "SN_20") (pintype "input"))
      (node (ref "U6") (pin "21") (pinfunction "SP_21") (pintype "input"))
      (node (ref "U6") (pin "25") (pinfunction "EP_25") (pintype "input"))
      (node (ref "U6") (pin "5") (pinfunction "GND_5") (pintype "input"))
      (node (ref "U7") (pin "1") (pinfunction "VSS_1") (pintype "input"))
    )
    (net (code "6") (name "MCU_MOTOR_DIR") (class "Default")
      (node (ref "R20") (pin "1") (pinfunction "1_1") (pintype "input"))
      (node (ref "U5") (pin "2") (pinfunction "1A_2") (pintype "input"))
      (node (ref "U8") (pin "3") (pinfunction "3_3") (pintype "unspecified"))
    )
    (net (code "7") (name "MCU_MOTOR_PWM") (class "Default")
      (node (ref "R21") (pin "1") (pinfunction "1_1") (pintype "input"))
      (node (ref "U5") (pin "5") (pinfunction "2A_5") (pintype "input"))
      (node (ref "U8") (pin "4") (pinfunction "4_4") (pintype "unspecified"))
    )
    (net (code "8") (name "MCU_SERVO_PWM_A") (class "Default")
      (node (ref "H2") (pin "1") (pinfunction "1_1") (pintype "unspecified"))
      (node (ref "U8") (pin "5") (pinfunction "5_5") (pintype "unspecified"))
    )
    (net (code "9") (name "MCU_SERVO_PWM_B") (class "Default")
      (node (ref "H2") (pin "3") (pinfunction "3_3") (pintype "unspecified"))
      (node (ref "U8") (pin "6") (pinfunction "6_6") (pintype "unspecified"))
    )
    (net (code "10") (name "MOTOR-A") (class "Default")
      (node (ref "CN4") (pin "1") (pinfunction "1_1") (pintype "input"))
      (node (ref "Q1") (pin "1") (pinfunction "S_1") (pintype "input"))
      (node (ref "Q1") (pin "2") (pinfunction "S_2") (pintype "input"))
      (node (ref "Q1") (pin "3") (pinfunction "S_3") (pintype "input"))
      (node (ref "Q3") (pin "5") (pinfunction "D_5") (pintype "input"))
      (node (ref "Q3") (pin "6") (pinfunction "D_6") (pintype "input"))
      (node (ref "Q3") (pin "7") (pinfunction "D_7") (pintype "input"))
      (node (ref "Q3") (pin "8") (pinfunction "D_8") (pintype "input"))
      (node (ref "Q3") (pin "9") (pinfunction "D_9") (pintype "input"))
      (node (ref "U6") (pin "23") (pinfunction "SH2_23") (pintype "input"))
    )
    (net (code "11") (name "MOTOR-B") (class "Default")
      (node (ref "CN4") (pin "2") (pinfunction "2_2") (pintype "input"))
      (node (ref "Q2") (pin "1") (pinfunction "S_1") (pintype "input"))
      (node (ref "Q2") (pin "2") (pinfunction "S_2") (pintype "input"))
      (node (ref "Q2") (pin "3") (pinfunction "S_3") (pintype "input"))
      (node (ref "Q4") (pin "5") (pinfunction "D_5") (pintype "input"))
      (node (ref "Q4") (pin "6") (pinfunction "D_6") (pintype "input"))
      (node (ref "Q4") (pin "7") (pinfunction "D_7") (pintype "input"))
      (node (ref "Q4") (pin "8") (pinfunction "D_8") (pintype "input"))
      (node (ref "Q4") (pin "9") (pinfunction "D_9") (pintype "input"))
      (node (ref "U6") (pin "18") (pinfunction "SH1_18") (pintype "input"))
    )
    (net (code "12") (name "NSLEEP") (class "Default")
      (node (ref "R22") (pin "2") (pinfunction "2_2") (pintype "input"))
      (node (ref "SW6") (pin "3") (pinfunction "3_3") (pintype "unspecified"))
      (node (ref "U6") (pin "13") (pinfunction "nSLEEP_13") (pintype "input"))
    )
    (net (code "13") (name "Net-(D1-C)") (class "Default")
      (node (ref "C5") (pin "1") (pinfunction "1_1") (pintype "input"))
      (node (ref "D1") (pin "1") (pinfunction "C_1") (pintype "unspecified"))
      (node (ref "L1") (pin "1") (pinfunction "1_1") (pintype "unspecified"))
      (node (ref "U1") (pin "8") (pinfunction "PH_8") (pintype "unspecified"))
    )
    (net (code "14") (name "Net-(D2-C)") (class "Default")
      (node (ref "C12") (pin "1") (pinfunction "1_1") (pintype "input"))
      (node (ref "D2") (pin "1") (pinfunction "C_1") (pintype "unspecified"))
      (node (ref "L2") (pin "1") (pinfunction "1_1") (pintype "unspecified"))
      (node (ref "U3") (pin "8") (pinfunction "PH_8") (pintype "unspecified"))
    )
    (net (code "15") (name "Net-(D3-K)") (class "Default")
      (node (ref "C19") (pin "2") (pinfunction "2_2") (pintype "input"))
      (node (ref "C20") (pin "2") (pinfunction "2_2") (pintype "input"))
      (node (ref "C21") (pin "2") (pinfunction "2_2") (pintype "input"))
      (node (ref "D3") (pin "1") (pinfunction "K_1") (pintype "input"))
      (node (ref "U6") (pin "1") (pinfunction "VM_1") (pintype "input"))
    )
    (net (code "16") (name "Net-(D4-Pad2)") (class "Default")
      (node (ref "D4") (pin "2") (pinfunction "2_2") (pintype "unspecified"))
      (node (ref "U10") (pin "2") (pinfunction "2_2") (pintype "unspecified"))
    )
    (net (code "17") (name "Net-(H1-Pad1)") (class "Default")
      (node (ref "H1") (pin "1") (pinfunction "1_1") (pintype "unspecified"))
      (node (ref "H2") (pin "2") (pinfunction "2_2") (pintype "unspecified"))
    )
    (net (code "18") (name "Net-(LED1-+)") (class "Default")
      (node (ref "LED1") (pin "1") (pinfunction "+_1") (pintype "unspecified"))
      (node (ref "R1") (pin "1") (pinfunction "1_1") (pintype "input"))
    )
    (net (code "19") (name "Net-(LED2-+)") (class "Default")
      (node (ref "LED2") (pin "1") (pinfunction "+_1") (pintype "unspecified"))
      (node (ref "R23") (pin "1") (pinfunction "1_1") (pintype "input"))
    )
    (net (code "20") (name "Net-(NSLEEP1-+)") (class "Default")
      (node (ref "NSLEEP1") (pin "1") (pinfunction "+_1") (pintype "unspecified"))
      (node (ref "R22") (pin "1") (pinfunction "1_1") (pintype "input"))
    )
    (net (code "21") (name "Net-(Q1-G)") (class "Default")
      (node (ref "Q1") (pin "4") (pinfunction "G_4") (pintype "input"))
      (node (ref "U6") (pin "24") (pinfunction "GH2_24") (pintype "input"))
    )
    (net (code "22") (name "Net-(Q2-G)") (class "Default")
      (node (ref "Q2") (pin "4") (pinfunction "G_4") (pintype "input"))
      (node (ref "U6") (pin "17") (pinfunction "GH1_17") (pintype "input"))
    )
    (net (code "23") (name "Net-(Q3-G)") (class "Default")
      (node (ref "Q3") (pin "4") (pinfunction "G_4") (pintype "input"))
      (node (ref "U6") (pin "22") (pinfunction "GL2_22") (pintype "input"))
    )
    (net (code "24") (name "Net-(Q4-G)") (class "Default")
      (node (ref "Q4") (pin "4") (pinfunction "G_4") (pintype "input"))
      (node (ref "U6") (pin "19") (pinfunction "GL1_19") (pintype "input"))
    )
    (net (code "25") (name "Net-(U1-BOOT)") (class "Default")
      (node (ref "C5") (pin "2") (pinfunction "2_2") (pintype "input"))
      (node (ref "U1") (pin "1") (pinfunction "BOOT_1") (pintype "unspecified"))
    )
    (net (code "26") (name "Net-(U1-VSENSE)") (class "Default")
      (node (ref "C6") (pin "2") (pinfunction "2_2") (pintype "input"))
      (node (ref "R2") (pin "2") (pinfunction "2_2") (pintype "input"))
      (node (ref "R3") (pin "1") (pinfunction "1_1") (pintype "input"))
      (node (ref "U1") (pin "4") (pinfunction "VSENSE_4") (pintype "unspecified"))
    )
    (net (code "27") (name "Net-(U3-BOOT)") (class "Default")
      (node (ref "C12") (pin "2") (pinfunction "2_2") (pintype "input"))
      (node (ref "U3") (pin "1") (pinfunction "BOOT_1") (pintype "unspecified"))
    )
    (net (code "28") (name "Net-(U3-VSENSE)") (class "Default")
      (node (ref "C13") (pin "2") (pinfunction "2_2") (pintype "input"))
      (node (ref "R4") (pin "1") (pinfunction "1_1") (pintype "input"))
      (node (ref "R5") (pin "2") (pinfunction "2_2") (pintype "input"))
      (node (ref "U3") (pin "4") (pinfunction "VSENSE_4") (pintype "unspecified"))
    )
    (net (code "29") (name "Net-(U6-AVDD)") (class "Default")
      (node (ref "C23") (pin "2") (pinfunction "2_2") (pintype "input"))
      (node (ref "U6") (pin "12") (pinfunction "IDRIVE_12") (pintype "input"))
      (node (ref "U6") (pin "6") (pinfunction "VREF_6") (pintype "input"))
      (node (ref "U6") (pin "7") (pinfunction "AVDD_7") (pintype "input"))
    )
    (net (code "30") (name "Net-(U6-CPH)") (class "Default")
      (node (ref "C22") (pin "2") (pinfunction "2_2") (pintype "input"))
      (node (ref "U6") (pin "3") (pinfunction "CPH_3") (pintype "input"))
    )
    (net (code "31") (name "Net-(U6-CPL)") (class "Default")
      (node (ref "C22") (pin "1") (pinfunction "1_1") (pintype "input"))
      (node (ref "U6") (pin "4") (pinfunction "CPL_4") (pintype "input"))
    )
    (net (code "32") (name "Net-(U6-VCP)") (class "Default")
      (node (ref "C21") (pin "1") (pinfunction "1_1") (pintype "input"))
      (node (ref "U6") (pin "2") (pinfunction "VCP_2") (pintype "input"))
    )
    (net (code "33") (name "Net-(U7-VOUT)") (class "Default")
      (node (ref "C26") (pin "2") (pinfunction "2_2") (pintype "input"))
      (node (ref "R23") (pin "2") (pinfunction "2_2") (pintype "input"))
      (node (ref "SW6") (pin "2") (pinfunction "2_2") (pintype "unspecified"))
      (node (ref "U7") (pin "2") (pinfunction "VOUT_2") (pintype "input"))
    )
    (net (code "34") (name "Net-(U9-+)") (class "Default")
      (node (ref "CN5") (pin "1") (pinfunction "1_1") (pintype "unspecified"))
      (node (ref "SW5") (pin "1") (pinfunction "1_1") (pintype "unspecified"))
      (node (ref "U9") (pin "2") (pinfunction "+_2") (pintype "input"))
    )
    (net (code "35") (name "PGND") (class "Default")
      (node (ref "C1") (pin "2") (pinfunction "2_2") (pintype "unspecified"))
      (node (ref "C33") (pin "2") (pinfunction "2_2") (pintype "unspecified"))
      (node (ref "C35") (pin "2") (pinfunction "2_2") (pintype "unspecified"))
      (node (ref "CN5") (pin "2") (pinfunction "2_2") (pintype "unspecified"))
      (node (ref "DC1") (pin "2") (pinfunction "2_2") (pintype "unspecified"))
      (node (ref "DC1") (pin "3") (pinfunction "3_3") (pintype "unspecified"))
      (node (ref "DC2") (pin "3") (pinfunction "3_3") (pintype "unspecified"))
      (node (ref "LED1") (pin "2") (pinfunction "-_2") (pintype "unspecified"))
      (node (ref "U11") (pin "1") (pinfunction "1_1") (pintype "unspecified"))
      (node (ref "U9") (pin "1") (pinfunction "-_1") (pintype "input"))
    )
    (net (code "36") (name "PH") (class "Default")
      (node (ref "U5") (pin "3") (pinfunction "1Y_3") (pintype "input"))
      (node (ref "U6") (pin "15") (pinfunction "PH_15") (pintype "input"))
    )
    (net (code "37") (name "SERVO_6V35") (class "Default")
      (node (ref "C14") (pin "1") (pinfunction "1_1") (pintype "input"))
      (node (ref "C15") (pin "1") (pinfunction "1_1") (pintype "input"))
      (node (ref "C27") (pin "1") (pinfunction "1_1") (pintype "input"))
      (node (ref "H1") (pin "2") (pinfunction "2_2") (pintype "unspecified"))
      (node (ref "L2") (pin "2") (pinfunction "2_2") (pintype "unspecified"))
      (node (ref "R4") (pin "2") (pinfunction "2_2") (pintype "input"))
    )
    (net (code "38") (name "VCC-12V-GSE") (class "Default")
      (node (ref "DC1") (pin "1") (pinfunction "1_1") (pintype "unspecified"))
      (node (ref "U10") (pin "1") (pinfunction "1_1") (pintype "unspecified"))
    )
    (net (code "39") (name "VCC_12V") (class "Default")
      (node (ref "C1") (pin "1") (pinfunction "1_1") (pintype "unspecified"))
      (node (ref "C10") (pin "2") (pinfunction "2_2") (pintype "unspecified"))
      (node (ref "C11") (pin "2") (pinfunction "2_2") (pintype "unspecified"))
      (node (ref "C25") (pin "2") (pinfunction "2_2") (pintype "input"))
      (node (ref "C3") (pin "2") (pinfunction "2_2") (pintype "unspecified"))
      (node (ref "C34") (pin "1") (pinfunction "1_1") (pintype "input"))
      (node (ref "C4") (pin "2") (pinfunction "2_2") (pintype "unspecified"))
      (node (ref "D3") (pin "2") (pinfunction "A_2") (pintype "input"))
      (node (ref "Q1") (pin "5") (pinfunction "D_5") (pintype "input"))
      (node (ref "Q1") (pin "6") (pinfunction "D_6") (pintype "input"))
      (node (ref "Q1") (pin "7") (pinfunction "D_7") (pintype "input"))
      (node (ref "Q1") (pin "8") (pinfunction "D_8") (pintype "input"))
      (node (ref "Q1") (pin "9") (pinfunction "D_9") (pintype "input"))
      (node (ref "Q2") (pin "5") (pinfunction "D_5") (pintype "input"))
      (node (ref "Q2") (pin "6") (pinfunction "D_6") (pintype "input"))
      (node (ref "Q2") (pin "7") (pinfunction "D_7") (pintype "input"))
      (node (ref "Q2") (pin "8") (pinfunction "D_8") (pintype "input"))
      (node (ref "Q2") (pin "9") (pinfunction "D_9") (pintype "input"))
      (node (ref "R1") (pin "2") (pinfunction "2_2") (pintype "input"))
      (node (ref "SW5") (pin "2") (pinfunction "2_2") (pintype "unspecified"))
      (node (ref "U1") (pin "7") (pinfunction "VIN_7") (pintype "unspecified"))
      (node (ref "U10") (pin "3") (pinfunction "3_3") (pintype "unspecified"))
      (node (ref "U3") (pin "7") (pinfunction "VIN_7") (pintype "unspecified"))
      (node (ref "U7") (pin "3") (pinfunction "VIN_3") (pintype "input"))
    )
    (net (code "40") (name "VCC_12V-1") (class "Default")
      (node (ref "C33") (pin "1") (pinfunction "1_1") (pintype "unspecified"))
      (node (ref "C35") (pin "1") (pinfunction "1_1") (pintype "unspecified"))
      (node (ref "D4") (pin "1") (pinfunction "1_1") (pintype "unspecified"))
      (node (ref "DC2") (pin "1") (pinfunction "1_1") (pintype "unspecified"))
    )
    (net (code "41") (name "unconnected-(SW6-Pad1)") (class "Default")
      (node (ref "SW6") (pin "1") (pinfunction "1_1") (pintype "unspecified+no_connect"))
    )
    (net (code "42") (name "unconnected-(U1-ENA-Pad5)") (class "Default")
      (node (ref "U1") (pin "5") (pinfunction "ENA_5") (pintype "unspecified+no_connect"))
    )
    (net (code "43") (name "unconnected-(U1-NC-Pad2)") (class "Default")
      (node (ref "U1") (pin "2") (pinfunction "NC_2") (pintype "unspecified+no_connect"))
    )
    (net (code "44") (name "unconnected-(U1-NC-Pad3)") (class "Default")
      (node (ref "U1") (pin "3") (pinfunction "NC_3") (pintype "unspecified+no_connect"))
    )
    (net (code "45") (name "unconnected-(U3-ENA-Pad5)") (class "Default")
      (node (ref "U3") (pin "5") (pinfunction "ENA_5") (pintype "unspecified+no_connect"))
    )
    (net (code "46") (name "unconnected-(U3-NC-Pad2)") (class "Default")
      (node (ref "U3") (pin "2") (pinfunction "NC_2") (pintype "unspecified+no_connect"))
    )
    (net (code "47") (name "unconnected-(U3-NC-Pad3)") (class "Default")
      (node (ref "U3") (pin "3") (pinfunction "NC_3") (pintype "unspecified+no_connect"))
    )
    (net (code "48") (name "unconnected-(U5-3A-Pad9)") (class "Default")
      (node (ref "U5") (pin "9") (pinfunction "3A_9") (pintype "input+no_connect"))
    )
    (net (code "49") (name "unconnected-(U5-3OE#-Pad10)") (class "Default")
      (node (ref "U5") (pin "10") (pinfunction "3OE#_10") (pintype "input+no_connect"))
    )
    (net (code "50") (name "unconnected-(U5-3Y-Pad8)") (class "Default")
      (node (ref "U5") (pin "8") (pinfunction "3Y_8") (pintype "input+no_connect"))
    )
    (net (code "51") (name "unconnected-(U5-4A-Pad12)") (class "Default")
      (node (ref "U5") (pin "12") (pinfunction "4A_12") (pintype "input+no_connect"))
    )
    (net (code "52") (name "unconnected-(U5-4OE#-Pad13)") (class "Default")
      (node (ref "U5") (pin "13") (pinfunction "4OE#_13") (pintype "input+no_connect"))
    )
    (net (code "53") (name "unconnected-(U5-4Y-Pad11)") (class "Default")
      (node (ref "U5") (pin "11") (pinfunction "4Y_11") (pintype "input+no_connect"))
    )
    (net (code "54") (name "unconnected-(U6-SNSOUT-Pad10)") (class "Default")
      (node (ref "U6") (pin "10") (pinfunction "SNSOUT_10") (pintype "input+no_connect"))
    )
    (net (code "55") (name "unconnected-(U6-SO-Pad11)") (class "Default")
      (node (ref "U6") (pin "11") (pinfunction "SO_11") (pintype "input+no_connect"))
    )
    (net (code "56") (name "unconnected-(U6-nFAULT-Pad9)") (class "Default")
      (node (ref "U6") (pin "9") (pinfunction "nFAULT_9") (pintype "input+no_connect"))
    )
  )
)
